# LPC.net
KiCad netlist of a schematic drawn in Altium Designer
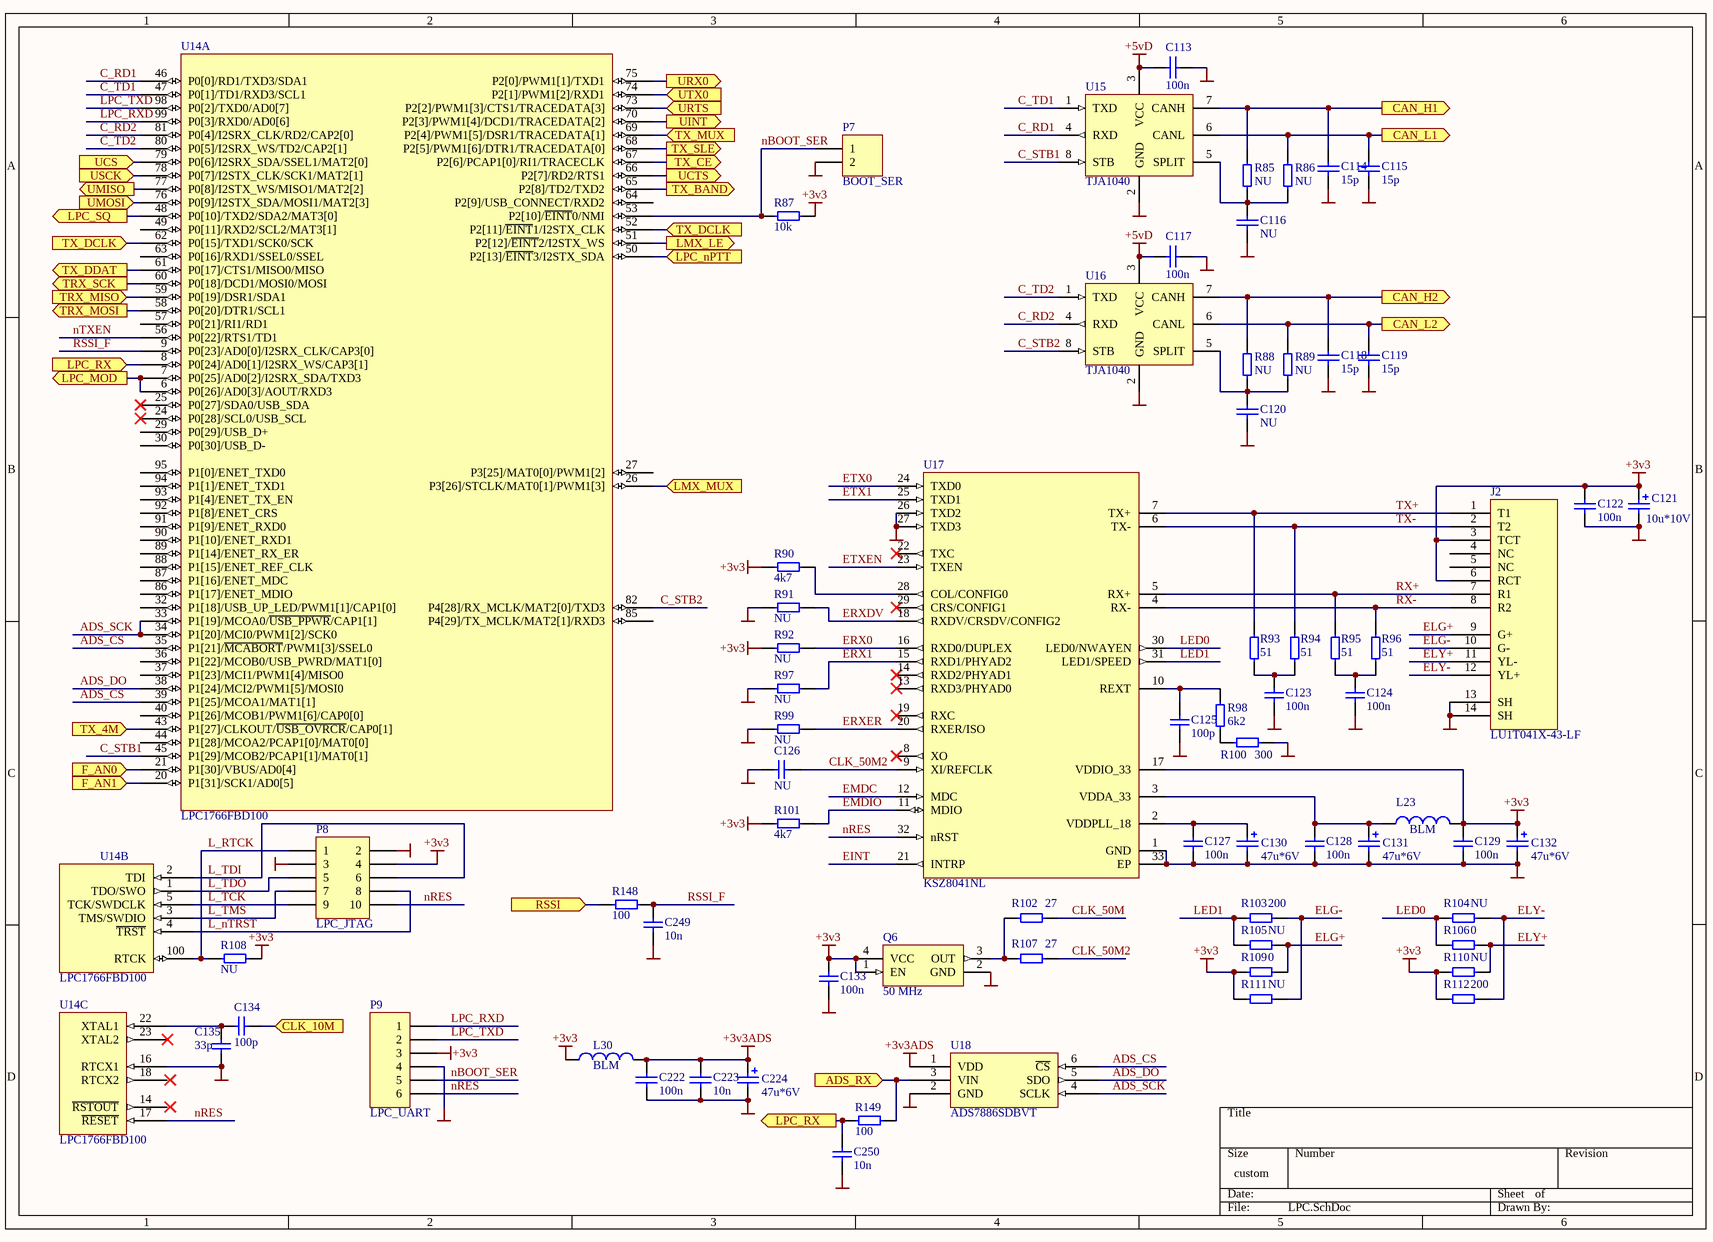
[diagram p0: LPC.SchDoc]

(export (version "E")
  (design (tool "Eeschema 10.0.6"))
  (components
    (comp (ref "C113")
      (value "100n")
      (footprint "CAPC1608N")
      (description "Capacitor")
      (fields (field (name "PUBLISHER") "Altium Limited"))
      (libsource (lib "") (part "Cap_1"))
    )
    (comp (ref "C114")
      (value "15p")
      (footprint "CAPC1608N")
      (description "Capacitor")
      (fields (field (name "PUBLISHER") "Altium Limited"))
      (libsource (lib "") (part "Cap_1"))
    )
    (comp (ref "C115")
      (value "15p")
      (footprint "CAPC1608N")
      (description "Capacitor")
      (fields (field (name "PUBLISHER") "Altium Limited"))
      (libsource (lib "") (part "Cap_1"))
    )
    (comp (ref "C116")
      (value "NU")
      (footprint "CAPC1608N")
      (description "Capacitor")
      (fields (field (name "PUBLISHER") "Altium Limited"))
      (libsource (lib "") (part "Cap_1"))
    )
    (comp (ref "C117")
      (value "100n")
      (footprint "CAPC1608N")
      (description "Capacitor")
      (fields (field (name "PUBLISHER") "Altium Limited"))
      (libsource (lib "") (part "Cap_1"))
    )
    (comp (ref "C118")
      (value "15p")
      (footprint "CAPC1608N")
      (description "Capacitor")
      (fields (field (name "PUBLISHER") "Altium Limited"))
      (libsource (lib "") (part "Cap_1"))
    )
    (comp (ref "C119")
      (value "15p")
      (footprint "CAPC1608N")
      (description "Capacitor")
      (fields (field (name "PUBLISHER") "Altium Limited"))
      (libsource (lib "") (part "Cap_1"))
    )
    (comp (ref "C120")
      (value "NU")
      (footprint "CAPC1608N")
      (description "Capacitor")
      (fields (field (name "PUBLISHER") "Altium Limited"))
      (libsource (lib "") (part "Cap_1"))
    )
    (comp (ref "C121")
      (value "10u*10V")
      (footprint "Case_A")
      (description "Polarized Capacitor (Surface Mount)")
      (fields (field (name "PUBLISHER") "Altium Limited"))
      (libsource (lib "Sch components") (part "Cap Pol"))
    )
    (comp (ref "C122")
      (value "100n")
      (footprint "CAPC1608N")
      (description "Capacitor")
      (fields (field (name "PUBLISHER") "Altium Limited"))
      (libsource (lib "") (part "Cap_1"))
    )
    (comp (ref "C123")
      (value "100n")
      (footprint "CAPC1608L")
      (description "Capacitor")
      (fields (field (name "PUBLISHER") "Altium Limited"))
      (libsource (lib "Sch components") (part "Cap"))
    )
    (comp (ref "C124")
      (value "100n")
      (footprint "CAPC1608L")
      (description "Capacitor")
      (fields (field (name "PUBLISHER") "Altium Limited"))
      (libsource (lib "Sch components") (part "Cap"))
    )
    (comp (ref "C125")
      (value "100p")
      (footprint "CAPC1608L")
      (description "Capacitor")
      (fields (field (name "PUBLISHER") "Altium Limited"))
      (libsource (lib "Sch components") (part "Cap"))
    )
    (comp (ref "C126")
      (value "NU")
      (footprint "CAPC1608L")
      (description "Capacitor")
      (fields (field (name "PUBLISHER") "Altium Limited"))
      (libsource (lib "Sch components") (part "Cap"))
    )
    (comp (ref "C127")
      (value "100n")
      (footprint "CAPC1608L")
      (description "Capacitor")
      (fields (field (name "PUBLISHER") "Altium Limited"))
      (libsource (lib "Sch components") (part "Cap"))
    )
    (comp (ref "C128")
      (value "100n")
      (footprint "CAPC1608L")
      (description "Capacitor")
      (fields (field (name "PUBLISHER") "Altium Limited"))
      (libsource (lib "Sch components") (part "Cap"))
    )
    (comp (ref "C129")
      (value "100n")
      (footprint "CAPC1608L")
      (description "Capacitor")
      (fields (field (name "PUBLISHER") "Altium Limited"))
      (libsource (lib "Sch components") (part "Cap"))
    )
    (comp (ref "C130")
      (value "47u*6V")
      (footprint "Case_A")
      (description "Polarized Capacitor (Surface Mount)")
      (fields (field (name "PUBLISHER") "Altium Limited"))
      (libsource (lib "Sch components") (part "Cap Pol"))
    )
    (comp (ref "C131")
      (value "47u*6V")
      (footprint "Case_A")
      (description "Polarized Capacitor (Surface Mount)")
      (fields (field (name "PUBLISHER") "Altium Limited"))
      (libsource (lib "Sch components") (part "Cap Pol"))
    )
    (comp (ref "C132")
      (value "47u*6V")
      (footprint "Case_A")
      (description "Polarized Capacitor (Surface Mount)")
      (fields (field (name "PUBLISHER") "Altium Limited"))
      (libsource (lib "Sch components") (part "Cap Pol"))
    )
    (comp (ref "C133")
      (value "100n")
      (footprint "CAPC1608L")
      (description "Capacitor")
      (fields (field (name "PUBLISHER") "Altium Limited"))
      (libsource (lib "Sch components") (part "Cap"))
    )
    (comp (ref "C134")
      (value "100p")
      (footprint "CAPC1608L")
      (description "Capacitor")
      (fields (field (name "PUBLISHER") "Altium Limited"))
      (libsource (lib "Sch components") (part "Cap"))
    )
    (comp (ref "C135")
      (value "33p")
      (footprint "CAPC1608L")
      (description "Capacitor")
      (fields (field (name "PUBLISHER") "Altium Limited"))
      (libsource (lib "Sch components") (part "Cap"))
    )
    (comp (ref "C222")
      (value "100n")
      (footprint "CAPC1608N")
      (description "Capacitor")
      (fields (field (name "PUBLISHER") "Altium Limited"))
      (libsource (lib "") (part "Cap_1"))
    )
    (comp (ref "C223")
      (value "10n")
      (footprint "CAPC1608N")
      (description "Capacitor")
      (fields (field (name "PUBLISHER") "Altium Limited"))
      (libsource (lib "") (part "Cap_1"))
    )
    (comp (ref "C224")
      (value "47u*6V")
      (footprint "Case_A")
      (description "Polarized Capacitor (Surface Mount)")
      (fields (field (name "PUBLISHER") "Altium Limited"))
      (libsource (lib "Sch components") (part "Cap Pol"))
    )
    (comp (ref "C249")
      (value "10n")
      (footprint "CAPC1608L")
      (description "Capacitor")
      (fields (field (name "PUBLISHER") "Altium Limited"))
      (libsource (lib "Sch components") (part "Cap"))
    )
    (comp (ref "C250")
      (value "10n")
      (footprint "CAPC1608L")
      (description "Capacitor")
      (fields (field (name "PUBLISHER") "Altium Limited"))
      (libsource (lib "Sch components") (part "Cap"))
    )
    (comp (ref "J2")
      (value "LU1T041X-43-LF")
      (footprint "JACK1.27-4H8C")
      (description "Ethernet 10/100 jack with magnetics")
      (libsource (lib "Sch components") (part "LU1T516-43"))
    )
    (comp (ref "L23")
      (value "BLM")
      (footprint "INDC2012L")
      (libsource (lib "Sch Components") (part "INDUCTOR"))
    )
    (comp (ref "L30")
      (value "BLM")
      (footprint "CAPC2012N")
      (description "Ferrite Bead")
      (fields (field (name "PUBLISHER") "Altium Limited"))
      (libsource (lib "Sch components") (part "Ferrite Bead"))
    )
    (comp (ref "P7")
      (value "BOOT_SER")
      (footprint "HDR1X2")
      (description "Header, 2-Pin")
      (fields (field (name "PUBLISHER") "Altium Limited"))
      (libsource (lib "Miscellaneous Connectors") (part "Header 2"))
    )
    (comp (ref "P8")
      (value "LPC_JTAG")
      (footprint "HDR2X5")
      (description "Header, 5-Pin, Dual row")
      (fields (field (name "PUBLISHER") "Altium Limited"))
      (libsource (lib "Miscellaneous Connectors") (part "Header 5X2"))
    )
    (comp (ref "P9")
      (value "LPC_UART")
      (footprint "HDR1X6")
      (description "Header, 6-Pin")
      (fields (field (name "PUBLISHER") "Altium Limited"))
      (libsource (lib "Miscellaneous Connectors") (part "Header 6"))
    )
    (comp (ref "Q6")
      (value "50 MHz")
      (footprint "XTAL_7.5_5mm")
      (description "Crystal Oscillator")
      (libsource (lib "Sch components") (part "XTAL_OSC"))
    )
    (comp (ref "R85")
      (value "NU")
      (footprint "RESC2012L")
      (description "Resistor")
      (fields (field (name "PUBLISHER") "Altium Limited"))
      (libsource (lib "Sch components") (part "Res"))
    )
    (comp (ref "R86")
      (value "NU")
      (footprint "RESC2012L")
      (description "Resistor")
      (fields (field (name "PUBLISHER") "Altium Limited"))
      (libsource (lib "Sch components") (part "Res"))
    )
    (comp (ref "R87")
      (value "10k")
      (footprint "RESC1608L")
      (description "Resistor")
      (fields (field (name "PUBLISHER") "Altium Limited"))
      (libsource (lib "Sch components") (part "Res"))
    )
    (comp (ref "R88")
      (value "NU")
      (footprint "RESC2012L")
      (description "Resistor")
      (fields (field (name "PUBLISHER") "Altium Limited"))
      (libsource (lib "Sch components") (part "Res"))
    )
    (comp (ref "R89")
      (value "NU")
      (footprint "RESC2012L")
      (description "Resistor")
      (fields (field (name "PUBLISHER") "Altium Limited"))
      (libsource (lib "Sch components") (part "Res"))
    )
    (comp (ref "R90")
      (value "4k7")
      (footprint "RESC1608L")
      (description "Resistor")
      (fields (field (name "PUBLISHER") "Altium Limited"))
      (libsource (lib "Sch components") (part "Res"))
    )
    (comp (ref "R91")
      (value "NU")
      (footprint "RESC1608L")
      (description "Resistor")
      (fields (field (name "PUBLISHER") "Altium Limited"))
      (libsource (lib "Sch components") (part "Res"))
    )
    (comp (ref "R92")
      (value "NU")
      (footprint "RESC1608L")
      (description "Resistor")
      (fields (field (name "PUBLISHER") "Altium Limited"))
      (libsource (lib "Sch components") (part "Res"))
    )
    (comp (ref "R93")
      (value "51")
      (footprint "RESC1608L")
      (description "Resistor")
      (fields (field (name "PUBLISHER") "Altium Limited"))
      (libsource (lib "Sch components") (part "Res"))
    )
    (comp (ref "R94")
      (value "51")
      (footprint "RESC1608L")
      (description "Resistor")
      (fields (field (name "PUBLISHER") "Altium Limited"))
      (libsource (lib "Sch components") (part "Res"))
    )
    (comp (ref "R95")
      (value "51")
      (footprint "RESC1608L")
      (description "Resistor")
      (fields (field (name "PUBLISHER") "Altium Limited"))
      (libsource (lib "Sch components") (part "Res"))
    )
    (comp (ref "R96")
      (value "51")
      (footprint "RESC1608L")
      (description "Resistor")
      (fields (field (name "PUBLISHER") "Altium Limited"))
      (libsource (lib "Sch components") (part "Res"))
    )
    (comp (ref "R97")
      (value "NU")
      (footprint "RESC1608L")
      (description "Resistor")
      (fields (field (name "PUBLISHER") "Altium Limited"))
      (libsource (lib "Sch components") (part "Res"))
    )
    (comp (ref "R98")
      (value "6k2")
      (footprint "RESC1608L")
      (description "Resistor")
      (fields (field (name "PUBLISHER") "Altium Limited"))
      (libsource (lib "Sch components") (part "Res"))
    )
    (comp (ref "R99")
      (value "NU")
      (footprint "RESC1608L")
      (description "Resistor")
      (fields (field (name "PUBLISHER") "Altium Limited"))
      (libsource (lib "Sch components") (part "Res"))
    )
    (comp (ref "R100")
      (value "300")
      (footprint "RESC1608L")
      (description "Resistor")
      (fields (field (name "PUBLISHER") "Altium Limited"))
      (libsource (lib "Sch components") (part "Res"))
    )
    (comp (ref "R101")
      (value "4k7")
      (footprint "RESC1608L")
      (description "Resistor")
      (fields (field (name "PUBLISHER") "Altium Limited"))
      (libsource (lib "Sch components") (part "Res"))
    )
    (comp (ref "R102")
      (value "27")
      (footprint "RESC1608L")
      (description "Resistor")
      (fields (field (name "PUBLISHER") "Altium Limited"))
      (libsource (lib "Sch components") (part "Res"))
    )
    (comp (ref "R103")
      (value "200")
      (footprint "RESC1608L")
      (description "Resistor")
      (fields (field (name "PUBLISHER") "Altium Limited"))
      (libsource (lib "Sch components") (part "Res"))
    )
    (comp (ref "R104")
      (value "NU")
      (footprint "RESC1608L")
      (description "Resistor")
      (fields (field (name "PUBLISHER") "Altium Limited"))
      (libsource (lib "Sch components") (part "Res"))
    )
    (comp (ref "R105")
      (value "NU")
      (footprint "RESC1608L")
      (description "Resistor")
      (fields (field (name "PUBLISHER") "Altium Limited"))
      (libsource (lib "Sch components") (part "Res"))
    )
    (comp (ref "R106")
      (value "0")
      (footprint "RESC1608L")
      (description "Resistor")
      (fields (field (name "PUBLISHER") "Altium Limited"))
      (libsource (lib "Sch components") (part "Res"))
    )
    (comp (ref "R107")
      (value "27")
      (footprint "RESC1608L")
      (description "Resistor")
      (fields (field (name "PUBLISHER") "Altium Limited"))
      (libsource (lib "Sch components") (part "Res"))
    )
    (comp (ref "R108")
      (value "NU")
      (footprint "RESC1608L")
      (description "Resistor")
      (fields (field (name "PUBLISHER") "Altium Limited"))
      (libsource (lib "Sch components") (part "Res"))
    )
    (comp (ref "R109")
      (value "0")
      (footprint "RESC1608L")
      (description "Resistor")
      (fields (field (name "PUBLISHER") "Altium Limited"))
      (libsource (lib "Sch components") (part "Res"))
    )
    (comp (ref "R110")
      (value "NU")
      (footprint "RESC1608L")
      (description "Resistor")
      (fields (field (name "PUBLISHER") "Altium Limited"))
      (libsource (lib "Sch components") (part "Res"))
    )
    (comp (ref "R111")
      (value "NU")
      (footprint "RESC1608L")
      (description "Resistor")
      (fields (field (name "PUBLISHER") "Altium Limited"))
      (libsource (lib "Sch components") (part "Res"))
    )
    (comp (ref "R112")
      (value "200")
      (footprint "RESC1608L")
      (description "Resistor")
      (fields (field (name "PUBLISHER") "Altium Limited"))
      (libsource (lib "Sch components") (part "Res"))
    )
    (comp (ref "R148")
      (value "100")
      (footprint "RESC1608L")
      (description "Resistor")
      (fields (field (name "PUBLISHER") "Altium Limited"))
      (libsource (lib "Sch components") (part "Res"))
    )
    (comp (ref "R149")
      (value "100")
      (footprint "RESC1608L")
      (description "Resistor")
      (fields (field (name "PUBLISHER") "Altium Limited"))
      (libsource (lib "Sch components") (part "Res"))
    )
    (comp (ref "U14")
      (value "LPC1766FBD100")
      (footprint "SOT407-1_L")
      (fields (field (name "PUBLISHER") "Altium Limited"))
      (libsource (lib "") (part "LPC1766FBD100_1"))
    )
    (comp (ref "U15")
      (value "TJA1040")
      (footprint "SOIC-150-8")
      (description "High-Speed CAN Tranceiver")
      (libsource (lib "Sch components") (part "TJA1040"))
    )
    (comp (ref "U16")
      (value "TJA1040")
      (footprint "SOIC-150-8")
      (description "High-Speed CAN Tranceiver")
      (libsource (lib "Sch components") (part "TJA1040"))
    )
    (comp (ref "U17")
      (value "KSZ8041NL")
      (footprint "QFN50P500X500-32WAN")
      (description "10Base-T/100Base-TX Physical Layer Transceiver")
      (libsource (lib "Sch components") (part "KSZ8041"))
    )
    (comp (ref "U18")
      (value "ADS7886SDBVT")
      (footprint "Pcb components:SOT26A-6N")
      (description "12-Bit, 1-MSPS, Micro-power ADC")
      (libsource (lib "Sch components") (part "ADS7886"))
    )
  )
  (nets
    (net (code "1") (name "+3v3") (class "Default")
      (node (ref "C121") (pin "1") (pinfunction "1_1") (pintype "passive"))
      (node (ref "C122") (pin "2") (pinfunction "2_2") (pintype "passive"))
      (node (ref "C129") (pin "2") (pinfunction "2_2") (pintype "passive"))
      (node (ref "C132") (pin "1") (pinfunction "1_1") (pintype "passive"))
      (node (ref "C133") (pin "2") (pinfunction "2_2") (pintype "passive"))
      (node (ref "J2") (pin "3") (pinfunction "TCT_3") (pintype "passive"))
      (node (ref "J2") (pin "6") (pinfunction "RCT_6") (pintype "passive"))
      (node (ref "L23") (pin "2") (pinfunction "2_2") (pintype "passive"))
      (node (ref "L30") (pin "1") (pinfunction "1_1") (pintype "passive"))
      (node (ref "P8") (pin "4") (pinfunction "4_4") (pintype "passive"))
      (node (ref "P9") (pin "3") (pinfunction "3_3") (pintype "passive"))
      (node (ref "Q6") (pin "1") (pinfunction "EN_1") (pintype "input"))
      (node (ref "Q6") (pin "4") (pinfunction "VCC_4") (pintype "power_in"))
      (node (ref "R101") (pin "2") (pinfunction "2_2") (pintype "passive"))
      (node (ref "R108") (pin "1") (pinfunction "1_1") (pintype "passive"))
      (node (ref "R109") (pin "2") (pinfunction "2_2") (pintype "passive"))
      (node (ref "R110") (pin "2") (pinfunction "2_2") (pintype "passive"))
      (node (ref "R111") (pin "2") (pinfunction "2_2") (pintype "passive"))
      (node (ref "R112") (pin "2") (pinfunction "2_2") (pintype "passive"))
      (node (ref "R87") (pin "2") (pinfunction "2_2") (pintype "passive"))
      (node (ref "R90") (pin "2") (pinfunction "2_2") (pintype "passive"))
      (node (ref "R92") (pin "2") (pinfunction "2_2") (pintype "passive"))
      (node (ref "U17") (pin "17") (pinfunction "VDDIO_33_17") (pintype "power_in"))
    )
    (net (code "2") (name "+3v3ADS") (class "Default")
      (node (ref "C222") (pin "2") (pinfunction "2_2") (pintype "passive"))
      (node (ref "C223") (pin "2") (pinfunction "2_2") (pintype "passive"))
      (node (ref "C224") (pin "1") (pinfunction "1_1") (pintype "passive"))
      (node (ref "L30") (pin "2") (pinfunction "2_2") (pintype "passive"))
      (node (ref "U18") (pin "1") (pinfunction "VDD_1") (pintype "power_in"))
    )
    (net (code "3") (name "+5vD") (class "Default")
      (node (ref "C113") (pin "1") (pinfunction "1_1") (pintype "passive"))
      (node (ref "C117") (pin "1") (pinfunction "1_1") (pintype "passive"))
      (node (ref "U15") (pin "3") (pinfunction "VCC_3") (pintype "power_in"))
      (node (ref "U16") (pin "3") (pinfunction "VCC_3") (pintype "power_in"))
    )
    (net (code "4") (name "/ADS_CS") (class "Default")
      (node (ref "U14") (pin "35") (pinfunction "P1[21]/~{MCABORT}/PWM1[3]/SSEL0_35") (pintype "bidirectional"))
      (node (ref "U14") (pin "39") (pinfunction "P1[25]/MCOA1/MAT1[1]_39") (pintype "bidirectional"))
      (node (ref "U18") (pin "6") (pinfunction "~{CS}_6") (pintype "input"))
    )
    (net (code "5") (name "/ADS_DO") (class "Default")
      (node (ref "U14") (pin "38") (pinfunction "P1[24]/MCI2/PWM1[5]/MOSI0_38") (pintype "bidirectional"))
      (node (ref "U18") (pin "5") (pinfunction "SDO_5") (pintype "output"))
    )
    (net (code "6") (name "/ADS_RX") (class "Default")
      (node (ref "R149") (pin "2") (pinfunction "2_2") (pintype "passive"))
      (node (ref "U18") (pin "3") (pinfunction "VIN_3") (pintype "passive"))
    )
    (net (code "7") (name "/ADS_SCK") (class "Default")
      (node (ref "U14") (pin "33") (pinfunction "P1[19]/MCOA0/~{USB_PPWR}/CAP1[1]_33") (pintype "bidirectional"))
      (node (ref "U14") (pin "34") (pinfunction "P1[20]/MCI0/PWM1[2]/SCK0_34") (pintype "bidirectional"))
      (node (ref "U18") (pin "4") (pinfunction "SCLK_4") (pintype "input"))
    )
    (net (code "8") (name "/CAN_H1") (class "Default")
      (node (ref "C114") (pin "2") (pinfunction "2_2") (pintype "passive"))
      (node (ref "R85") (pin "1") (pinfunction "1_1") (pintype "passive"))
      (node (ref "U15") (pin "7") (pinfunction "CANH_7") (pintype "passive"))
    )
    (net (code "9") (name "/CAN_H2") (class "Default")
      (node (ref "C118") (pin "2") (pinfunction "2_2") (pintype "passive"))
      (node (ref "R88") (pin "1") (pinfunction "1_1") (pintype "passive"))
      (node (ref "U16") (pin "7") (pinfunction "CANH_7") (pintype "passive"))
    )
    (net (code "10") (name "/CAN_L1") (class "Default")
      (node (ref "C115") (pin "2") (pinfunction "2_2") (pintype "passive"))
      (node (ref "R86") (pin "1") (pinfunction "1_1") (pintype "passive"))
      (node (ref "U15") (pin "6") (pinfunction "CANL_6") (pintype "passive"))
    )
    (net (code "11") (name "/CAN_L2") (class "Default")
      (node (ref "C119") (pin "2") (pinfunction "2_2") (pintype "passive"))
      (node (ref "R89") (pin "1") (pinfunction "1_1") (pintype "passive"))
      (node (ref "U16") (pin "6") (pinfunction "CANL_6") (pintype "passive"))
    )
    (net (code "12") (name "/CLK_10M") (class "Default")
      (node (ref "C134") (pin "2") (pinfunction "2_2") (pintype "passive"))
    )
    (net (code "13") (name "/CLK_50M") (class "Default")
      (node (ref "R102") (pin "2") (pinfunction "2_2") (pintype "passive"))
    )
    (net (code "14") (name "/CLK_50M2") (class "Default")
      (node (ref "C126") (pin "1") (pinfunction "1_1") (pintype "passive"))
      (node (ref "R107") (pin "2") (pinfunction "2_2") (pintype "passive"))
      (node (ref "U17") (pin "9") (pinfunction "XI/REFCLK_9") (pintype "input"))
    )
    (net (code "15") (name "/C_RD1") (class "Default")
      (node (ref "U14") (pin "46") (pinfunction "P0[0]/RD1/TXD3/SDA1_46") (pintype "bidirectional"))
      (node (ref "U15") (pin "4") (pinfunction "RXD_4") (pintype "output"))
    )
    (net (code "16") (name "/C_RD2") (class "Default")
      (node (ref "U14") (pin "81") (pinfunction "P0[4]/I2SRX_CLK/RD2/CAP2[0]_81") (pintype "bidirectional"))
      (node (ref "U16") (pin "4") (pinfunction "RXD_4") (pintype "output"))
    )
    (net (code "17") (name "/C_STB1") (class "Default")
      (node (ref "U14") (pin "45") (pinfunction "P1[29]/MCOB2/PCAP1[1]/MAT0[1]_45") (pintype "bidirectional"))
      (node (ref "U15") (pin "8") (pinfunction "STB_8") (pintype "input"))
    )
    (net (code "18") (name "/C_STB2") (class "Default")
      (node (ref "U14") (pin "82") (pinfunction "P4[28]/RX_MCLK/MAT2[0]/TXD3_82") (pintype "bidirectional"))
      (node (ref "U16") (pin "8") (pinfunction "STB_8") (pintype "input"))
    )
    (net (code "19") (name "/C_TD1") (class "Default")
      (node (ref "U14") (pin "47") (pinfunction "P0[1]/TD1/RXD3/SCL1_47") (pintype "bidirectional"))
      (node (ref "U15") (pin "1") (pinfunction "TXD_1") (pintype "input"))
    )
    (net (code "20") (name "/C_TD2") (class "Default")
      (node (ref "U14") (pin "80") (pinfunction "P0[5]/I2SRX_WS/TD2/CAP2[1]_80") (pintype "bidirectional"))
      (node (ref "U16") (pin "1") (pinfunction "TXD_1") (pintype "input"))
    )
    (net (code "21") (name "/EINT") (class "Default")
      (node (ref "U17") (pin "21") (pinfunction "INTRP_21") (pintype "output"))
    )
    (net (code "22") (name "/ELG+") (class "Default")
      (node (ref "J2") (pin "9") (pinfunction "G+_9") (pintype "passive"))
      (node (ref "R105") (pin "1") (pinfunction "1_1") (pintype "passive"))
      (node (ref "R109") (pin "1") (pinfunction "1_1") (pintype "passive"))
    )
    (net (code "23") (name "/ELG-") (class "Default")
      (node (ref "J2") (pin "10") (pinfunction "G-_10") (pintype "passive"))
      (node (ref "R103") (pin "1") (pinfunction "1_1") (pintype "passive"))
      (node (ref "R111") (pin "1") (pinfunction "1_1") (pintype "passive"))
    )
    (net (code "24") (name "/ELY+") (class "Default")
      (node (ref "J2") (pin "11") (pinfunction "YL-_11") (pintype "passive"))
      (node (ref "R106") (pin "1") (pinfunction "1_1") (pintype "passive"))
      (node (ref "R110") (pin "1") (pinfunction "1_1") (pintype "passive"))
    )
    (net (code "25") (name "/ELY-") (class "Default")
      (node (ref "J2") (pin "12") (pinfunction "YL+_12") (pintype "passive"))
      (node (ref "R104") (pin "1") (pinfunction "1_1") (pintype "passive"))
      (node (ref "R112") (pin "1") (pinfunction "1_1") (pintype "passive"))
    )
    (net (code "26") (name "/EMDC") (class "Default")
      (node (ref "U17") (pin "12") (pinfunction "MDC_12") (pintype "input"))
    )
    (net (code "27") (name "/EMDIO") (class "Default")
      (node (ref "R101") (pin "1") (pinfunction "1_1") (pintype "passive"))
      (node (ref "U17") (pin "11") (pinfunction "MDIO_11") (pintype "bidirectional"))
    )
    (net (code "28") (name "/ERX0") (class "Default")
      (node (ref "R92") (pin "1") (pinfunction "1_1") (pintype "passive"))
      (node (ref "U17") (pin "16") (pinfunction "RXD0/DUPLEX_16") (pintype "output"))
    )
    (net (code "29") (name "/ERX1") (class "Default")
      (node (ref "R97") (pin "1") (pinfunction "1_1") (pintype "passive"))
      (node (ref "U17") (pin "15") (pinfunction "RXD1/PHYAD2_15") (pintype "output"))
    )
    (net (code "30") (name "/ERXDV") (class "Default")
      (node (ref "R91") (pin "1") (pinfunction "1_1") (pintype "passive"))
      (node (ref "U17") (pin "18") (pinfunction "RXDV/CRSDV/CONFIG2_18") (pintype "output"))
    )
    (net (code "31") (name "/ERXER") (class "Default")
      (node (ref "R99") (pin "1") (pinfunction "1_1") (pintype "passive"))
      (node (ref "U17") (pin "20") (pinfunction "RXER/ISO_20") (pintype "output"))
    )
    (net (code "32") (name "/ETX0") (class "Default")
      (node (ref "U17") (pin "24") (pinfunction "TXD0_24") (pintype "input"))
    )
    (net (code "33") (name "/ETX1") (class "Default")
      (node (ref "U17") (pin "25") (pinfunction "TXD1_25") (pintype "input"))
    )
    (net (code "34") (name "/ETXEN") (class "Default")
      (node (ref "U17") (pin "23") (pinfunction "TXEN_23") (pintype "input"))
    )
    (net (code "35") (name "/F_AN0") (class "Default")
      (node (ref "U14") (pin "21") (pinfunction "P1[30]/VBUS/AD0[4]_21") (pintype "bidirectional"))
    )
    (net (code "36") (name "/F_AN1") (class "Default")
      (node (ref "U14") (pin "20") (pinfunction "P1[31]/SCK1/AD0[5]_20") (pintype "bidirectional"))
    )
    (net (code "37") (name "/LED0") (class "Default")
      (node (ref "R104") (pin "2") (pinfunction "2_2") (pintype "passive"))
      (node (ref "R106") (pin "2") (pinfunction "2_2") (pintype "passive"))
      (node (ref "U17") (pin "30") (pinfunction "LED0/NWAYEN_30") (pintype "output"))
    )
    (net (code "38") (name "/LED1") (class "Default")
      (node (ref "R103") (pin "2") (pinfunction "2_2") (pintype "passive"))
      (node (ref "R105") (pin "2") (pinfunction "2_2") (pintype "passive"))
      (node (ref "U17") (pin "31") (pinfunction "LED1/SPEED_31") (pintype "output"))
    )
    (net (code "39") (name "/LMX_LE") (class "Default")
      (node (ref "U14") (pin "51") (pinfunction "P2[12]/~{EINT}2/I2STX_WS_51") (pintype "bidirectional"))
    )
    (net (code "40") (name "/LMX_MUX") (class "Default")
      (node (ref "U14") (pin "26") (pinfunction "P3[26]/STCLK/MAT0[1]/PWM1[3]_26") (pintype "bidirectional"))
    )
    (net (code "41") (name "/LPC_MOD") (class "Default")
      (node (ref "U14") (pin "6") (pinfunction "P0[26]/AD0[3]/AOUT/RXD3_6") (pintype "bidirectional"))
      (node (ref "U14") (pin "7") (pinfunction "P0[25]/AD0[2]/I2SRX_SDA/TXD3_7") (pintype "bidirectional"))
    )
    (net (code "42") (name "/LPC_RX") (class "Default")
      (node (ref "C250") (pin "2") (pinfunction "2_2") (pintype "passive"))
      (node (ref "R149") (pin "1") (pinfunction "1_1") (pintype "passive"))
      (node (ref "U14") (pin "8") (pinfunction "P0[24]/AD0[1]/I2SRX_WS/CAP3[1]_8") (pintype "bidirectional"))
    )
    (net (code "43") (name "/LPC_RXD") (class "Default")
      (node (ref "P9") (pin "1") (pinfunction "1_1") (pintype "passive"))
      (node (ref "U14") (pin "99") (pinfunction "P0[3]/RXD0/AD0[6]_99") (pintype "bidirectional"))
    )
    (net (code "44") (name "/LPC_SQ") (class "Default")
      (node (ref "U14") (pin "48") (pinfunction "P0[10]/TXD2/SDA2/MAT3[0]_48") (pintype "bidirectional"))
    )
    (net (code "45") (name "/LPC_TXD") (class "Default")
      (node (ref "P9") (pin "2") (pinfunction "2_2") (pintype "passive"))
      (node (ref "U14") (pin "98") (pinfunction "P0[2]/TXD0/AD0[7]_98") (pintype "bidirectional"))
    )
    (net (code "46") (name "/LPC_nPTT") (class "Default")
      (node (ref "U14") (pin "50") (pinfunction "P2[13]/~{EINT}3/I2STX_SDA_50") (pintype "bidirectional"))
    )
    (net (code "47") (name "/L_RTCK") (class "Default")
      (node (ref "P8") (pin "1") (pinfunction "1_1") (pintype "passive"))
      (node (ref "R108") (pin "2") (pinfunction "2_2") (pintype "passive"))
      (node (ref "U14") (pin "100") (pinfunction "RTCK_100") (pintype "bidirectional"))
    )
    (net (code "48") (name "/L_TCK") (class "Default")
      (node (ref "P8") (pin "9") (pinfunction "9_9") (pintype "passive"))
      (node (ref "U14") (pin "5") (pinfunction "TCK/SWDCLK_5") (pintype "input"))
    )
    (net (code "49") (name "/L_TDI") (class "Default")
      (node (ref "P8") (pin "6") (pinfunction "6_6") (pintype "passive"))
      (node (ref "U14") (pin "2") (pinfunction "TDI_2") (pintype "input"))
    )
    (net (code "50") (name "/L_TDO") (class "Default")
      (node (ref "P8") (pin "5") (pinfunction "5_5") (pintype "passive"))
      (node (ref "U14") (pin "1") (pinfunction "TDO/SWO_1") (pintype "output"))
    )
    (net (code "51") (name "/L_TMS") (class "Default")
      (node (ref "P8") (pin "7") (pinfunction "7_7") (pintype "passive"))
      (node (ref "U14") (pin "3") (pinfunction "TMS/SWDIO_3") (pintype "input"))
    )
    (net (code "52") (name "/L_nTRST") (class "Default")
      (node (ref "P8") (pin "8") (pinfunction "8_8") (pintype "passive"))
      (node (ref "U14") (pin "4") (pinfunction "~{TRST}_4") (pintype "input"))
    )
    (net (code "53") (name "/RSSI") (class "Default")
      (node (ref "R148") (pin "1") (pinfunction "1_1") (pintype "passive"))
    )
    (net (code "54") (name "/RSSI_F") (class "Default")
      (node (ref "C249") (pin "2") (pinfunction "2_2") (pintype "passive"))
      (node (ref "R148") (pin "2") (pinfunction "2_2") (pintype "passive"))
      (node (ref "U14") (pin "9") (pinfunction "P0[23]/AD0[0]/I2SRX_CLK/CAP3[0]_9") (pintype "bidirectional"))
    )
    (net (code "55") (name "/RX+") (class "Default")
      (node (ref "J2") (pin "7") (pinfunction "R1_7") (pintype "passive"))
      (node (ref "R95") (pin "2") (pinfunction "2_2") (pintype "passive"))
      (node (ref "U17") (pin "5") (pinfunction "RX+_5") (pintype "passive"))
    )
    (net (code "56") (name "/RX-") (class "Default")
      (node (ref "J2") (pin "8") (pinfunction "R2_8") (pintype "passive"))
      (node (ref "R96") (pin "2") (pinfunction "2_2") (pintype "passive"))
      (node (ref "U17") (pin "4") (pinfunction "RX-_4") (pintype "passive"))
    )
    (net (code "57") (name "/TRX_MISO") (class "Default")
      (node (ref "U14") (pin "59") (pinfunction "P0[19]/DSR1/SDA1_59") (pintype "bidirectional"))
    )
    (net (code "58") (name "/TRX_MOSI") (class "Default")
      (node (ref "U14") (pin "58") (pinfunction "P0[20]/DTR1/SCL1_58") (pintype "bidirectional"))
    )
    (net (code "59") (name "/TRX_SCK") (class "Default")
      (node (ref "U14") (pin "60") (pinfunction "P0[18]/DCD1/MOSI0/MOSI_60") (pintype "bidirectional"))
    )
    (net (code "60") (name "/TX+") (class "Default")
      (node (ref "J2") (pin "1") (pinfunction "T1_1") (pintype "passive"))
      (node (ref "R93") (pin "2") (pinfunction "2_2") (pintype "passive"))
      (node (ref "U17") (pin "7") (pinfunction "TX+_7") (pintype "passive"))
    )
    (net (code "61") (name "/TX-") (class "Default")
      (node (ref "J2") (pin "2") (pinfunction "T2_2") (pintype "passive"))
      (node (ref "R94") (pin "2") (pinfunction "2_2") (pintype "passive"))
      (node (ref "U17") (pin "6") (pinfunction "TX-_6") (pintype "passive"))
    )
    (net (code "62") (name "/TX_4M") (class "Default")
      (node (ref "U14") (pin "43") (pinfunction "P1[27]/CLKOUT/~{USB_OVRCR}/CAP0[1]_43") (pintype "bidirectional"))
    )
    (net (code "63") (name "/TX_BAND") (class "Default")
      (node (ref "U14") (pin "65") (pinfunction "P2[8]/TD2/TXD2_65") (pintype "bidirectional"))
    )
    (net (code "64") (name "/TX_CE") (class "Default")
      (node (ref "U14") (pin "67") (pinfunction "P2[6]/PCAP1[0]/RI1/TRACECLK_67") (pintype "bidirectional"))
    )
    (net (code "65") (name "/TX_DCLK") (class "Default")
      (node (ref "U14") (pin "52") (pinfunction "P2[11]/~{EINT}1/I2STX_CLK_52") (pintype "bidirectional"))
      (node (ref "U14") (pin "62") (pinfunction "P0[15]/TXD1/SCK0/SCK_62") (pintype "bidirectional"))
    )
    (net (code "66") (name "/TX_DDAT") (class "Default")
      (node (ref "U14") (pin "61") (pinfunction "P0[17]/CTS1/MISO0/MISO_61") (pintype "bidirectional"))
    )
    (net (code "67") (name "/TX_MUX") (class "Default")
      (node (ref "U14") (pin "69") (pinfunction "P2[4]/PWM1[5]/DSR1/TRACEDATA[1]_69") (pintype "bidirectional"))
    )
    (net (code "68") (name "/TX_SLE") (class "Default")
      (node (ref "U14") (pin "68") (pinfunction "P2[5]/PWM1[6]/DTR1/TRACEDATA[0]_68") (pintype "bidirectional"))
    )
    (net (code "69") (name "/UCS") (class "Default")
      (node (ref "U14") (pin "79") (pinfunction "P0[6]/I2SRX_SDA/SSEL1/MAT2[0]_79") (pintype "bidirectional"))
    )
    (net (code "70") (name "/UCTS") (class "Default")
      (node (ref "U14") (pin "66") (pinfunction "P2[7]/RD2/RTS1_66") (pintype "bidirectional"))
    )
    (net (code "71") (name "/UINT") (class "Default")
      (node (ref "U14") (pin "70") (pinfunction "P2[3]/PWM1[4]/DCD1/TRACEDATA[2]_70") (pintype "bidirectional"))
    )
    (net (code "72") (name "/UMISO") (class "Default")
      (node (ref "U14") (pin "77") (pinfunction "P0[8]/I2STX_WS/MISO1/MAT2[2]_77") (pintype "bidirectional"))
    )
    (net (code "73") (name "/UMOSI") (class "Default")
      (node (ref "U14") (pin "76") (pinfunction "P0[9]/I2STX_SDA/MOSI1/MAT2[3]_76") (pintype "bidirectional"))
    )
    (net (code "74") (name "/URTS") (class "Default")
      (node (ref "U14") (pin "73") (pinfunction "P2[2]/PWM1[3]/CTS1/TRACEDATA[3]_73") (pintype "bidirectional"))
    )
    (net (code "75") (name "/URX0") (class "Default")
      (node (ref "U14") (pin "75") (pinfunction "P2[0]/PWM1[1]/TXD1_75") (pintype "bidirectional"))
    )
    (net (code "76") (name "/USCK") (class "Default")
      (node (ref "U14") (pin "78") (pinfunction "P0[7]/I2STX_CLK/SCK1/MAT2[1]_78") (pintype "bidirectional"))
    )
    (net (code "77") (name "/UTX0") (class "Default")
      (node (ref "U14") (pin "74") (pinfunction "P2[1]/PWM1[2]/RXD1_74") (pintype "bidirectional"))
    )
    (net (code "78") (name "/nBOOT_SER") (class "Default")
      (node (ref "P7") (pin "1") (pinfunction "1_1") (pintype "passive"))
      (node (ref "P9") (pin "5") (pinfunction "5_5") (pintype "passive"))
      (node (ref "R87") (pin "1") (pinfunction "1_1") (pintype "passive"))
      (node (ref "U14") (pin "53") (pinfunction "P2[10]/~{EINT}0/NMI_53") (pintype "bidirectional"))
    )
    (net (code "79") (name "/nRES") (class "Default")
      (node (ref "P8") (pin "10") (pinfunction "10_10") (pintype "passive"))
      (node (ref "P9") (pin "6") (pinfunction "6_6") (pintype "passive"))
      (node (ref "U14") (pin "17") (pinfunction "~{RESET}_17") (pintype "input"))
      (node (ref "U17") (pin "32") (pinfunction "nRST_32") (pintype "input"))
    )
    (net (code "80") (name "/nTXEN") (class "Default")
      (node (ref "U14") (pin "56") (pinfunction "P0[22]/RTS1/TD1_56") (pintype "bidirectional"))
    )
    (net (code "81") (name "GND") (class "Default")
      (node (ref "C113") (pin "2") (pinfunction "2_2") (pintype "passive"))
      (node (ref "C114") (pin "1") (pinfunction "1_1") (pintype "passive"))
      (node (ref "C115") (pin "1") (pinfunction "1_1") (pintype "passive"))
      (node (ref "C116") (pin "1") (pinfunction "1_1") (pintype "passive"))
      (node (ref "C117") (pin "2") (pinfunction "2_2") (pintype "passive"))
      (node (ref "C118") (pin "1") (pinfunction "1_1") (pintype "passive"))
      (node (ref "C119") (pin "1") (pinfunction "1_1") (pintype "passive"))
      (node (ref "C120") (pin "1") (pinfunction "1_1") (pintype "passive"))
      (node (ref "C121") (pin "2") (pinfunction "2_2") (pintype "passive"))
      (node (ref "C122") (pin "1") (pinfunction "1_1") (pintype "passive"))
      (node (ref "C123") (pin "1") (pinfunction "1_1") (pintype "passive"))
      (node (ref "C124") (pin "1") (pinfunction "1_1") (pintype "passive"))
      (node (ref "C125") (pin "1") (pinfunction "1_1") (pintype "passive"))
      (node (ref "C126") (pin "2") (pinfunction "2_2") (pintype "passive"))
      (node (ref "C127") (pin "1") (pinfunction "1_1") (pintype "passive"))
      (node (ref "C128") (pin "1") (pinfunction "1_1") (pintype "passive"))
      (node (ref "C129") (pin "1") (pinfunction "1_1") (pintype "passive"))
      (node (ref "C130") (pin "2") (pinfunction "2_2") (pintype "passive"))
      (node (ref "C131") (pin "2") (pinfunction "2_2") (pintype "passive"))
      (node (ref "C132") (pin "2") (pinfunction "2_2") (pintype "passive"))
      (node (ref "C133") (pin "1") (pinfunction "1_1") (pintype "passive"))
      (node (ref "C135") (pin "1") (pinfunction "1_1") (pintype "passive"))
      (node (ref "C222") (pin "1") (pinfunction "1_1") (pintype "passive"))
      (node (ref "C223") (pin "1") (pinfunction "1_1") (pintype "passive"))
      (node (ref "C224") (pin "2") (pinfunction "2_2") (pintype "passive"))
      (node (ref "C249") (pin "1") (pinfunction "1_1") (pintype "passive"))
      (node (ref "C250") (pin "1") (pinfunction "1_1") (pintype "passive"))
      (node (ref "J2") (pin "13") (pinfunction "SH_13") (pintype "passive"))
      (node (ref "J2") (pin "14") (pinfunction "SH_14") (pintype "passive"))
      (node (ref "P7") (pin "2") (pinfunction "2_2") (pintype "passive"))
      (node (ref "P8") (pin "2") (pinfunction "2_2") (pintype "passive"))
      (node (ref "P8") (pin "3") (pinfunction "3_3") (pintype "passive"))
      (node (ref "P9") (pin "4") (pinfunction "4_4") (pintype "passive"))
      (node (ref "Q6") (pin "2") (pinfunction "GND_2") (pintype "power_in"))
      (node (ref "R100") (pin "1") (pinfunction "1_1") (pintype "passive"))
      (node (ref "R91") (pin "2") (pinfunction "2_2") (pintype "passive"))
      (node (ref "R97") (pin "2") (pinfunction "2_2") (pintype "passive"))
      (node (ref "R99") (pin "2") (pinfunction "2_2") (pintype "passive"))
      (node (ref "U14") (pin "16") (pinfunction "RTCX1_16") (pintype "input"))
      (node (ref "U15") (pin "2") (pinfunction "GND_2") (pintype "power_in"))
      (node (ref "U16") (pin "2") (pinfunction "GND_2") (pintype "power_in"))
      (node (ref "U17") (pin "1") (pinfunction "GND_1") (pintype "power_in"))
      (node (ref "U17") (pin "26") (pinfunction "TXD2_26") (pintype "input"))
      (node (ref "U17") (pin "27") (pinfunction "TXD3_27") (pintype "input"))
      (node (ref "U17") (pin "33") (pinfunction "EP_33") (pintype "power_in"))
      (node (ref "U18") (pin "2") (pinfunction "GND_2") (pintype "power_in"))
    )
    (net (code "82") (name "Net-(C123-Pad2)") (class "Default")
      (node (ref "C123") (pin "2") (pinfunction "2_2") (pintype "passive"))
      (node (ref "R93") (pin "1") (pinfunction "1_1") (pintype "passive"))
      (node (ref "R94") (pin "1") (pinfunction "1_1") (pintype "passive"))
    )
    (net (code "83") (name "Net-(C124-Pad2)") (class "Default")
      (node (ref "C124") (pin "2") (pinfunction "2_2") (pintype "passive"))
      (node (ref "R95") (pin "1") (pinfunction "1_1") (pintype "passive"))
      (node (ref "R96") (pin "1") (pinfunction "1_1") (pintype "passive"))
    )
    (net (code "84") (name "Net-(Q6-OUT)") (class "Default")
      (node (ref "Q6") (pin "3") (pinfunction "OUT_3") (pintype "output"))
      (node (ref "R102") (pin "1") (pinfunction "1_1") (pintype "passive"))
      (node (ref "R107") (pin "1") (pinfunction "1_1") (pintype "passive"))
    )
    (net (code "85") (name "Net-(R100-Pad2)") (class "Default")
      (node (ref "R100") (pin "2") (pinfunction "2_2") (pintype "passive"))
      (node (ref "R98") (pin "1") (pinfunction "1_1") (pintype "passive"))
    )
    (net (code "86") (name "Net-(U14C-XTAL1)") (class "Default")
      (node (ref "C134") (pin "1") (pinfunction "1_1") (pintype "passive"))
      (node (ref "C135") (pin "2") (pinfunction "2_2") (pintype "passive"))
      (node (ref "U14") (pin "22") (pinfunction "XTAL1_22") (pintype "input"))
    )
    (net (code "87") (name "Net-(U15-SPLIT)") (class "Default")
      (node (ref "C116") (pin "2") (pinfunction "2_2") (pintype "passive"))
      (node (ref "R85") (pin "2") (pinfunction "2_2") (pintype "passive"))
      (node (ref "R86") (pin "2") (pinfunction "2_2") (pintype "passive"))
      (node (ref "U15") (pin "5") (pinfunction "SPLIT_5") (pintype "passive"))
    )
    (net (code "88") (name "Net-(U16-SPLIT)") (class "Default")
      (node (ref "C120") (pin "2") (pinfunction "2_2") (pintype "passive"))
      (node (ref "R88") (pin "2") (pinfunction "2_2") (pintype "passive"))
      (node (ref "R89") (pin "2") (pinfunction "2_2") (pintype "passive"))
      (node (ref "U16") (pin "5") (pinfunction "SPLIT_5") (pintype "passive"))
    )
    (net (code "89") (name "Net-(U17-COL{slash}CONFIG0)") (class "Default")
      (node (ref "R90") (pin "1") (pinfunction "1_1") (pintype "passive"))
      (node (ref "U17") (pin "28") (pinfunction "COL/CONFIG0_28") (pintype "output"))
    )
    (net (code "90") (name "Net-(U17-REXT)") (class "Default")
      (node (ref "C125") (pin "2") (pinfunction "2_2") (pintype "passive"))
      (node (ref "R98") (pin "2") (pinfunction "2_2") (pintype "passive"))
      (node (ref "U17") (pin "10") (pinfunction "REXT_10") (pintype "passive"))
    )
    (net (code "91") (name "Net-(U17-VDDA_33)") (class "Default")
      (node (ref "C128") (pin "2") (pinfunction "2_2") (pintype "passive"))
      (node (ref "C131") (pin "1") (pinfunction "1_1") (pintype "passive"))
      (node (ref "L23") (pin "1") (pinfunction "1_1") (pintype "passive"))
      (node (ref "U17") (pin "3") (pinfunction "VDDA_33_3") (pintype "passive"))
    )
    (net (code "92") (name "Net-(U17-VDDPLL_18)") (class "Default")
      (node (ref "C127") (pin "2") (pinfunction "2_2") (pintype "passive"))
      (node (ref "C130") (pin "1") (pinfunction "1_1") (pintype "passive"))
      (node (ref "U17") (pin "2") (pinfunction "VDDPLL_18_2") (pintype "passive"))
    )
    (net (code "93") (name "unconnected-(J2-NC-Pad4)") (class "Default")
      (node (ref "J2") (pin "4") (pinfunction "NC_4") (pintype "passive"))
    )
    (net (code "94") (name "unconnected-(J2-NC-Pad5)") (class "Default")
      (node (ref "J2") (pin "5") (pinfunction "NC_5") (pintype "passive"))
    )
    (net (code "95") (name "unconnected-(U14A-P0[11]{slash}RXD2{slash}SCL2{slash}MAT3[1]-Pad49)") (class "Default")
      (node (ref "U14") (pin "49") (pinfunction "P0[11]/RXD2/SCL2/MAT3[1]_49") (pintype "bidirectional"))
    )
    (net (code "96") (name "unconnected-(U14A-P0[16]{slash}RXD1{slash}SSEL0{slash}SSEL-Pad63)") (class "Default")
      (node (ref "U14") (pin "63") (pinfunction "P0[16]/RXD1/SSEL0/SSEL_63") (pintype "bidirectional"))
    )
    (net (code "97") (name "unconnected-(U14A-P0[21]{slash}RI1{slash}RD1-Pad57)") (class "Default")
      (node (ref "U14") (pin "57") (pinfunction "P0[21]/RI1/RD1_57") (pintype "bidirectional"))
    )
    (net (code "98") (name "unconnected-(U14A-P0[27]{slash}SDA0{slash}USB_SDA-Pad25)") (class "Default")
      (node (ref "U14") (pin "25") (pinfunction "P0[27]/SDA0/USB_SDA_25") (pintype "bidirectional+no_connect"))
    )
    (net (code "99") (name "unconnected-(U14A-P0[28]{slash}SCL0{slash}USB_SCL-Pad24)") (class "Default")
      (node (ref "U14") (pin "24") (pinfunction "P0[28]/SCL0/USB_SCL_24") (pintype "bidirectional+no_connect"))
    )
    (net (code "100") (name "unconnected-(U14A-P0[29]{slash}USB_D+-Pad29)") (class "Default")
      (node (ref "U14") (pin "29") (pinfunction "P0[29]/USB_D+_29") (pintype "bidirectional"))
    )
    (net (code "101") (name "unconnected-(U14A-P0[30]{slash}USB_D--Pad30)") (class "Default")
      (node (ref "U14") (pin "30") (pinfunction "P0[30]/USB_D-_30") (pintype "bidirectional"))
    )
    (net (code "102") (name "unconnected-(U14A-P1[0]{slash}ENET_TXD0-Pad95)") (class "Default")
      (node (ref "U14") (pin "95") (pinfunction "P1[0]/ENET_TXD0_95") (pintype "bidirectional"))
    )
    (net (code "103") (name "unconnected-(U14A-P1[1]{slash}ENET_TXD1-Pad94)") (class "Default")
      (node (ref "U14") (pin "94") (pinfunction "P1[1]/ENET_TXD1_94") (pintype "bidirectional"))
    )
    (net (code "104") (name "unconnected-(U14A-P1[4]{slash}ENET_TX_EN-Pad93)") (class "Default")
      (node (ref "U14") (pin "93") (pinfunction "P1[4]/ENET_TX_EN_93") (pintype "bidirectional"))
    )
    (net (code "105") (name "unconnected-(U14A-P1[8]{slash}ENET_CRS-Pad92)") (class "Default")
      (node (ref "U14") (pin "92") (pinfunction "P1[8]/ENET_CRS_92") (pintype "bidirectional"))
    )
    (net (code "106") (name "unconnected-(U14A-P1[9]{slash}ENET_RXD0-Pad91)") (class "Default")
      (node (ref "U14") (pin "91") (pinfunction "P1[9]/ENET_RXD0_91") (pintype "bidirectional"))
    )
    (net (code "107") (name "unconnected-(U14A-P1[10]{slash}ENET_RXD1-Pad90)") (class "Default")
      (node (ref "U14") (pin "90") (pinfunction "P1[10]/ENET_RXD1_90") (pintype "bidirectional"))
    )
    (net (code "108") (name "unconnected-(U14A-P1[14]{slash}ENET_RX_ER-Pad89)") (class "Default")
      (node (ref "U14") (pin "89") (pinfunction "P1[14]/ENET_RX_ER_89") (pintype "bidirectional"))
    )
    (net (code "109") (name "unconnected-(U14A-P1[15]{slash}ENET_REF_CLK-Pad88)") (class "Default")
      (node (ref "U14") (pin "88") (pinfunction "P1[15]/ENET_REF_CLK_88") (pintype "bidirectional"))
    )
    (net (code "110") (name "unconnected-(U14A-P1[16]{slash}ENET_MDC-Pad87)") (class "Default")
      (node (ref "U14") (pin "87") (pinfunction "P1[16]/ENET_MDC_87") (pintype "bidirectional"))
    )
    (net (code "111") (name "unconnected-(U14A-P1[17]{slash}ENET_MDIO-Pad86)") (class "Default")
      (node (ref "U14") (pin "86") (pinfunction "P1[17]/ENET_MDIO_86") (pintype "bidirectional"))
    )
    (net (code "112") (name "unconnected-(U14A-P1[18]{slash}USB_UP_LED{slash}PWM1[1]{slash}CAP1[0]-Pad32)") (class "Default")
      (node (ref "U14") (pin "32") (pinfunction "P1[18]/USB_UP_LED/PWM1[1]/CAP1[0]_32") (pintype "bidirectional"))
    )
    (net (code "113") (name "unconnected-(U14A-P1[22]{slash}MCOB0{slash}USB_PWRD{slash}MAT1[0]-Pad36)") (class "Default")
      (node (ref "U14") (pin "36") (pinfunction "P1[22]/MCOB0/USB_PWRD/MAT1[0]_36") (pintype "bidirectional"))
    )
    (net (code "114") (name "unconnected-(U14A-P1[23]{slash}MCI1{slash}PWM1[4]{slash}MISO0-Pad37)") (class "Default")
      (node (ref "U14") (pin "37") (pinfunction "P1[23]/MCI1/PWM1[4]/MISO0_37") (pintype "bidirectional"))
    )
    (net (code "115") (name "unconnected-(U14A-P1[26]{slash}MCOB1{slash}PWM1[6]{slash}CAP0[0]-Pad40)") (class "Default")
      (node (ref "U14") (pin "40") (pinfunction "P1[26]/MCOB1/PWM1[6]/CAP0[0]_40") (pintype "bidirectional"))
    )
    (net (code "116") (name "unconnected-(U14A-P1[28]{slash}MCOA2{slash}PCAP1[0]{slash}MAT0[0]-Pad44)") (class "Default")
      (node (ref "U14") (pin "44") (pinfunction "P1[28]/MCOA2/PCAP1[0]/MAT0[0]_44") (pintype "bidirectional"))
    )
    (net (code "117") (name "unconnected-(U14A-P2[9]{slash}USB_CONNECT{slash}RXD2-Pad64)") (class "Default")
      (node (ref "U14") (pin "64") (pinfunction "P2[9]/USB_CONNECT/RXD2_64") (pintype "bidirectional"))
    )
    (net (code "118") (name "unconnected-(U14A-P3[25]{slash}MAT0[0]{slash}PWM1[2]-Pad27)") (class "Default")
      (node (ref "U14") (pin "27") (pinfunction "P3[25]/MAT0[0]/PWM1[2]_27") (pintype "bidirectional"))
    )
    (net (code "119") (name "unconnected-(U14A-P4[29]{slash}TX_MCLK{slash}MAT2[1]{slash}RXD3-Pad85)") (class "Default")
      (node (ref "U14") (pin "85") (pinfunction "P4[29]/TX_MCLK/MAT2[1]/RXD3_85") (pintype "bidirectional"))
    )
    (net (code "120") (name "unconnected-(U14C-RTCX2-Pad18)") (class "Default")
      (node (ref "U14") (pin "18") (pinfunction "RTCX2_18") (pintype "output"))
    )
    (net (code "121") (name "unconnected-(U14C-XTAL2-Pad23)") (class "Default")
      (node (ref "U14") (pin "23") (pinfunction "XTAL2_23") (pintype "output+no_connect"))
    )
    (net (code "122") (name "unconnected-(U14C-~{RSTOUT}-Pad14)") (class "Default")
      (node (ref "U14") (pin "14") (pinfunction "~{RSTOUT}_14") (pintype "output"))
    )
    (net (code "123") (name "unconnected-(U17-CRS{slash}CONFIG1-Pad29)") (class "Default")
      (node (ref "U17") (pin "29") (pinfunction "CRS/CONFIG1_29") (pintype "output+no_connect"))
    )
    (net (code "124") (name "unconnected-(U17-RXC-Pad19)") (class "Default")
      (node (ref "U17") (pin "19") (pinfunction "RXC_19") (pintype "output+no_connect"))
    )
    (net (code "125") (name "unconnected-(U17-RXD2{slash}PHYAD1-Pad14)") (class "Default")
      (node (ref "U17") (pin "14") (pinfunction "RXD2/PHYAD1_14") (pintype "output+no_connect"))
    )
    (net (code "126") (name "unconnected-(U17-RXD3{slash}PHYAD0-Pad13)") (class "Default")
      (node (ref "U17") (pin "13") (pinfunction "RXD3/PHYAD0_13") (pintype "output+no_connect"))
    )
    (net (code "127") (name "unconnected-(U17-TXC-Pad22)") (class "Default")
      (node (ref "U17") (pin "22") (pinfunction "TXC_22") (pintype "output+no_connect"))
    )
    (net (code "128") (name "unconnected-(U17-XO-Pad8)") (class "Default")
      (node (ref "U17") (pin "8") (pinfunction "XO_8") (pintype "output+no_connect"))
    )
  )
)
